# 3_amplifier.net
KiCad netlist of a schematic drawn in Altium Designer
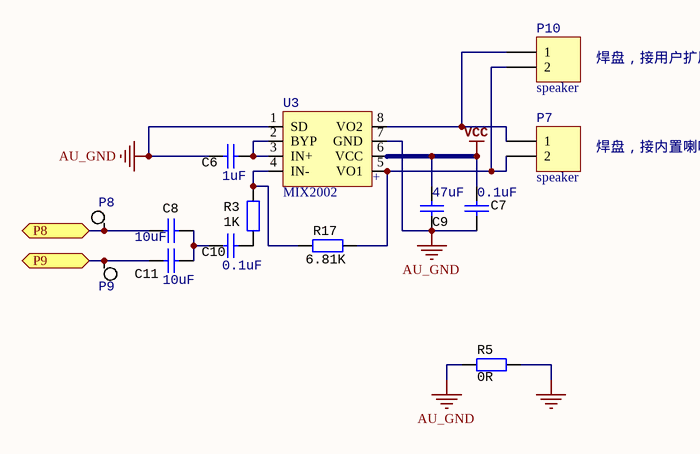
[diagram p0: 3 amplifier.SchDoc]

(export (version "E")
  (design (tool "Eeschema 10.0.6"))
  (components
    (comp (ref "C6")
      (value "1uF")
      (footprint "0402")
      (description "CAP, CERM, 0.01uF, 100V, +/-5%, X7R, 0603")
      (fields (field (name "PARTNUMBER") "06031C103JAT2A") (field (name "MANUFACTURER") "AVX"))
      (libsource (lib "03.常用器件") (part "CAP1_npol"))
    )
    (comp (ref "C7")
      (value "0.1uF")
      (footprint "0402")
      (description "CAP, CERM, 0.01uF, 100V, +/-5%, X7R, 0603")
      (fields (field (name "PARTNUMBER") "06031C103JAT2A") (field (name "MANUFACTURER") "AVX"))
      (libsource (lib "03.常用器件") (part "CAP1_npol"))
    )
    (comp (ref "C8")
      (value "10uF")
      (footprint "0603")
      (description "CAP, CERM, 0.01uF, 100V, +/-5%, X7R, 0603")
      (fields (field (name "PARTNUMBER") "06031C103JAT2A") (field (name "MANUFACTURER") "AVX"))
      (libsource (lib "03.常用器件") (part "CAP1_npol"))
    )
    (comp (ref "C9")
      (value "47uF")
      (footprint "0805")
      (description "CAP, CERM, 0.01uF, 100V, +/-5%, X7R, 0603")
      (fields (field (name "PARTNUMBER") "06031C103JAT2A") (field (name "MANUFACTURER") "AVX"))
      (libsource (lib "03.常用器件") (part "CAP1_npol"))
    )
    (comp (ref "C10")
      (value "0.1uF")
      (footprint "0402")
      (description "CAP, CERM, 0.01uF, 100V, +/-5%, X7R, 0603")
      (fields (field (name "PARTNUMBER") "06031C103JAT2A") (field (name "MANUFACTURER") "AVX"))
      (libsource (lib "03.常用器件") (part "CAP1_npol"))
    )
    (comp (ref "C11")
      (value "10uF")
      (footprint "0603")
      (description "CAP, CERM, 0.01uF, 100V, +/-5%, X7R, 0603")
      (fields (field (name "PARTNUMBER") "06031C103JAT2A") (field (name "MANUFACTURER") "AVX"))
      (libsource (lib "03.常用器件") (part "CAP1_npol"))
    )
    (comp (ref "P7")
      (value "speaker")
      (footprint "焊盘")
      (description "Header, 2-Pin")
      (fields (field (name "PUBLISHER") "Altium Limited"))
      (libsource (lib "Miscellaneous Connectors") (part "Header 2"))
    )
    (comp (ref "P8")
      (value "~")
      (footprint "测试点")
      (description "Test Point")
      (libsource (lib "my_Schlib") (part "TP"))
    )
    (comp (ref "P9")
      (value "~")
      (footprint "测试点")
      (description "Test Point")
      (libsource (lib "my_Schlib") (part "TP"))
    )
    (comp (ref "P10")
      (value "speaker")
      (footprint "2PIN/2.0MM座子")
      (description "Header, 2-Pin")
      (fields (field (name "PUBLISHER") "Altium Limited"))
      (libsource (lib "Miscellaneous Connectors") (part "Header 2"))
    )
    (comp (ref "R3")
      (value "1K")
      (footprint "0402")
      (description "RES, 1.0k ohm, 5%, 0.1W, 0603")
      (fields
        (field (name "PARTNUMBER") "RC0603JR-071KL")
        (field (name "MANUFACTURER") "Yageo America")
        (field (name "PUBLISHER") "Texas Instruments")
      )
      (libsource (lib "") (part "RES1_2"))
    )
    (comp (ref "R5")
      (value "0R")
      (footprint "0402")
      (description "RES, 1.0k ohm, 5%, 0.1W, 0603")
      (fields
        (field (name "PARTNUMBER") "RC0603JR-071KL")
        (field (name "MANUFACTURER") "Yageo America")
        (field (name "PUBLISHER") "Texas Instruments")
      )
      (libsource (lib "03.常用器件") (part "RES1"))
    )
    (comp (ref "R17")
      (value "6.81K")
      (footprint "0402")
      (description "RES, 1.0k ohm, 5%, 0.1W, 0603")
      (fields
        (field (name "PARTNUMBER") "RC0603JR-071KL")
        (field (name "MANUFACTURER") "Yageo America")
        (field (name "PUBLISHER") "Texas Instruments")
      )
      (libsource (lib "") (part "RES1_1"))
    )
    (comp (ref "U3") (value "MIX2002") (footprint "SOP-8") (libsource (lib "Schlib1") (part "MIX2002")))
  )
  (nets
    (net (code "1") (name "/P8") (class "Default")
      (node (ref "C8") (pin "2") (pinfunction "2_2") (pintype "passive"))
      (node (ref "P8") (pin "1") (pinfunction "1_1") (pintype "passive"))
    )
    (net (code "2") (name "/P9") (class "Default")
      (node (ref "C11") (pin "2") (pinfunction "2_2") (pintype "passive"))
      (node (ref "P9") (pin "1") (pinfunction "1_1") (pintype "passive"))
    )
    (net (code "3") (name "<NO NET>") (class "Default")
      (node (ref "R5") (pin "1") (pinfunction "1_1") (pintype "passive"))
    )
    (net (code "4") (name "AU_GND") (class "Default")
      (node (ref "C6") (pin "1") (pinfunction "1_1") (pintype "passive"))
      (node (ref "C7") (pin "2") (pinfunction "2_2") (pintype "passive"))
      (node (ref "C9") (pin "2") (pinfunction "2_2") (pintype "passive"))
      (node (ref "R5") (pin "2") (pinfunction "2_2") (pintype "passive"))
      (node (ref "U3") (pin "1") (pinfunction "SD_1") (pintype "passive"))
      (node (ref "U3") (pin "7") (pinfunction "GND_7") (pintype "passive"))
    )
    (net (code "5") (name "Net-(C10-Pad1)") (class "Default")
      (node (ref "C10") (pin "1") (pinfunction "1_1") (pintype "passive"))
      (node (ref "C11") (pin "1") (pinfunction "1_1") (pintype "passive"))
      (node (ref "C8") (pin "1") (pinfunction "1_1") (pintype "passive"))
    )
    (net (code "6") (name "Net-(C10-Pad2)") (class "Default")
      (node (ref "C10") (pin "2") (pinfunction "2_2") (pintype "passive"))
      (node (ref "R3") (pin "1") (pinfunction "1_1") (pintype "passive"))
    )
    (net (code "7") (name "Net-(U3-BYP)") (class "Default")
      (node (ref "C6") (pin "2") (pinfunction "2_2") (pintype "passive"))
      (node (ref "U3") (pin "2") (pinfunction "BYP_2") (pintype "passive"))
      (node (ref "U3") (pin "3") (pinfunction "IN+_3") (pintype "passive"))
    )
    (net (code "8") (name "Net-(U3-IN-)") (class "Default")
      (node (ref "R17") (pin "1") (pinfunction "1_1") (pintype "passive"))
      (node (ref "R3") (pin "2") (pinfunction "2_2") (pintype "passive"))
      (node (ref "U3") (pin "4") (pinfunction "IN-_4") (pintype "passive"))
    )
    (net (code "9") (name "Net-(U3-VO1)") (class "Default")
      (node (ref "P10") (pin "2") (pinfunction "2_2") (pintype "passive"))
      (node (ref "P7") (pin "2") (pinfunction "2_2") (pintype "passive"))
      (node (ref "R17") (pin "2") (pinfunction "2_2") (pintype "passive"))
      (node (ref "U3") (pin "5") (pinfunction "VO1_5") (pintype "passive"))
    )
    (net (code "10") (name "Net-(U3-VO2)") (class "Default")
      (node (ref "P10") (pin "1") (pinfunction "1_1") (pintype "passive"))
      (node (ref "P7") (pin "1") (pinfunction "1_1") (pintype "passive"))
      (node (ref "U3") (pin "8") (pinfunction "VO2_8") (pintype "passive"))
    )
    (net (code "11") (name "VCC") (class "Default")
      (node (ref "C7") (pin "1") (pinfunction "1_1") (pintype "passive"))
      (node (ref "C9") (pin "1") (pinfunction "1_1") (pintype "passive"))
      (node (ref "U3") (pin "6") (pinfunction "VCC_6") (pintype "passive"))
    )
  )
)
